# pinoccio-motion.net
KiCad netlist of a schematic drawn in EAGLE
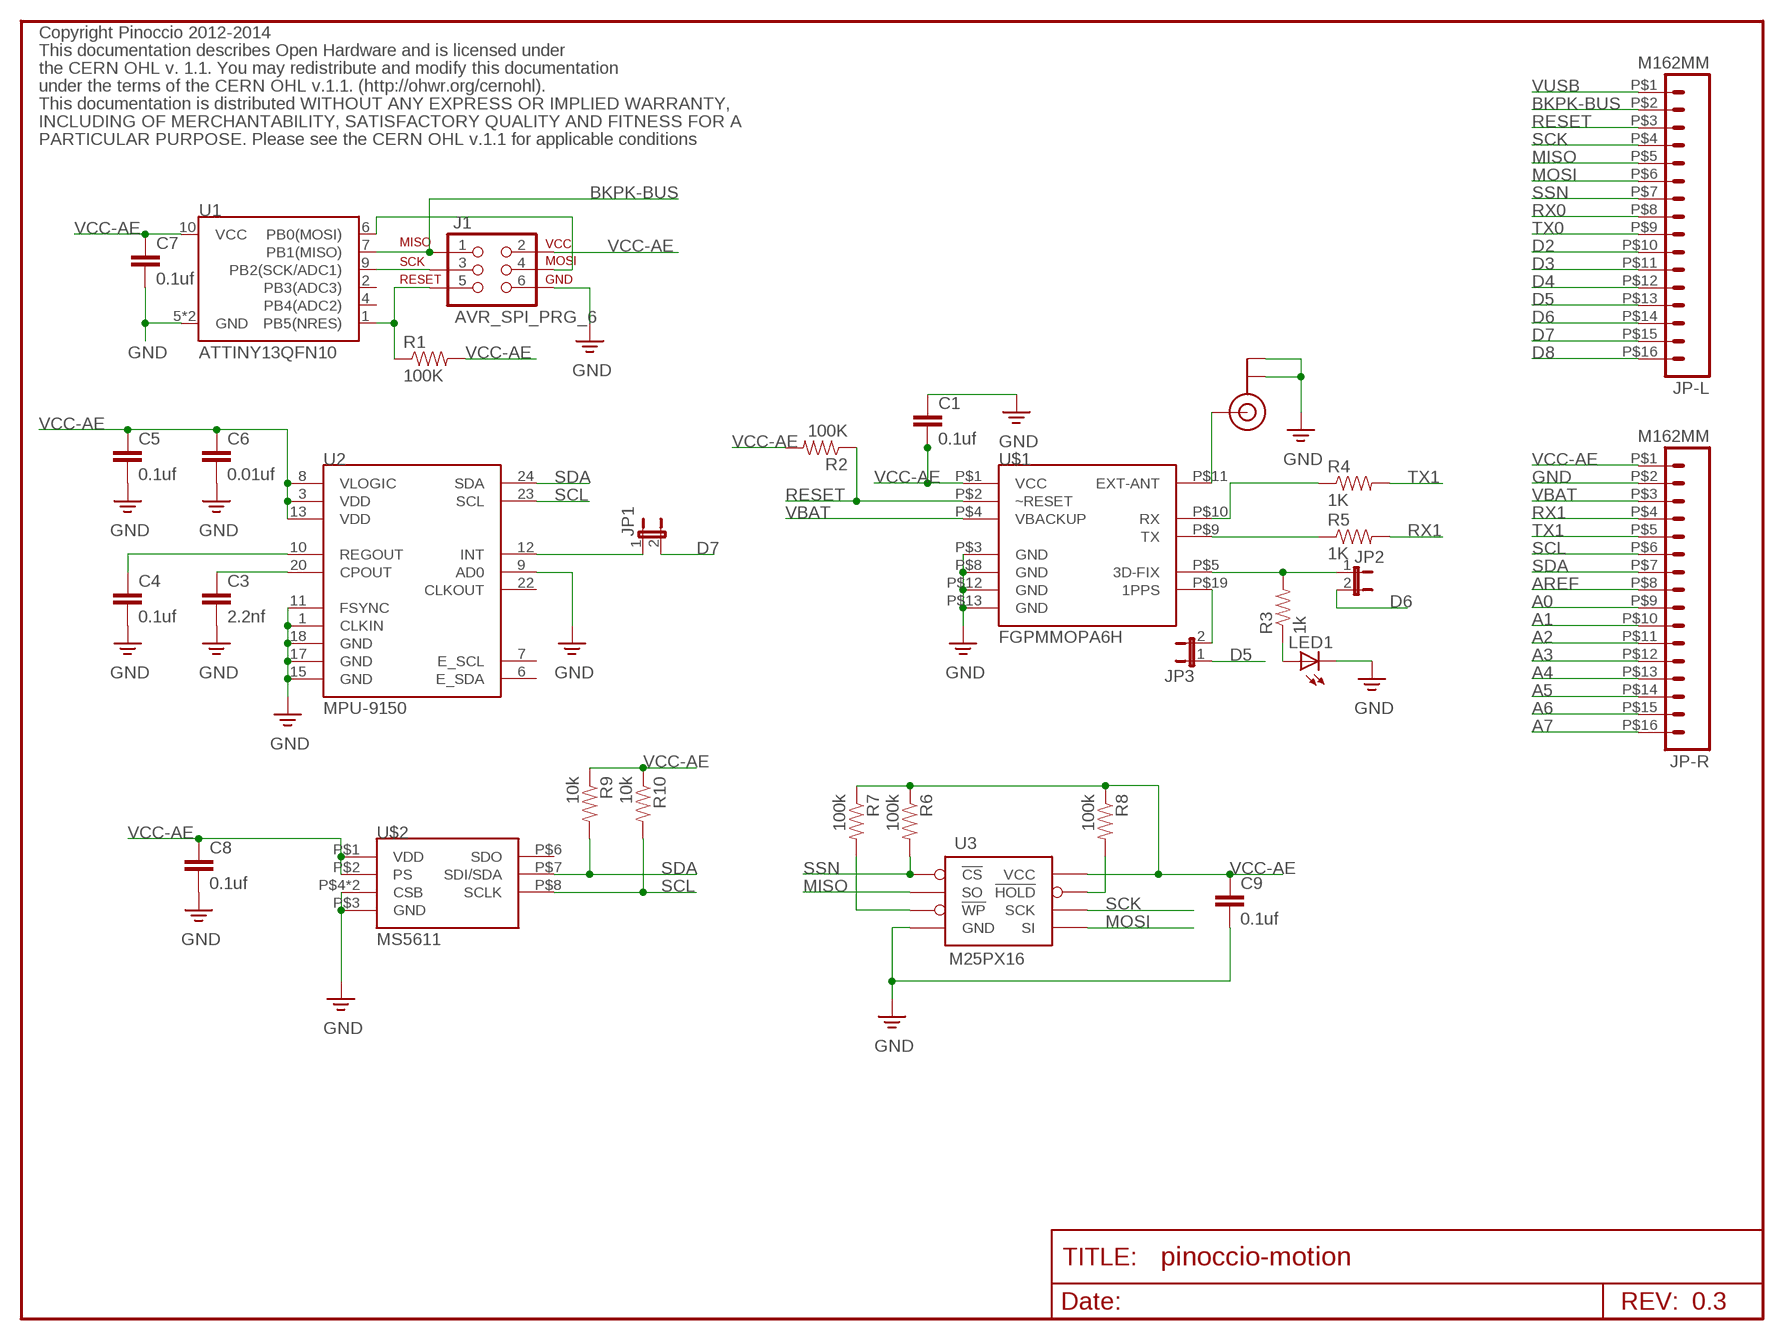
[diagram p0: schematic, sheet 1]

(export (version "E")
  (design (tool "Eeschema 10.0.6"))
  (components
    (comp (ref "C1")
      (value "0.1uf")
      (footprint "eagle-import:0402-CAP")
      (libsource (lib "eagle-import") (part "CAP0402-CAP"))
    )
    (comp (ref "C3")
      (value "2.2nf")
      (footprint "eagle-import:0603-CAP")
      (libsource (lib "eagle-import") (part "CAP0603-CAP"))
    )
    (comp (ref "C4")
      (value "0.1uf")
      (footprint "eagle-import:0402-CAP")
      (libsource (lib "eagle-import") (part "CAP0402-CAP"))
    )
    (comp (ref "C5")
      (value "0.1uf")
      (footprint "eagle-import:0402-CAP")
      (libsource (lib "eagle-import") (part "CAP0402-CAP"))
    )
    (comp (ref "C6")
      (value "0.01uf")
      (footprint "eagle-import:0402-CAP")
      (libsource (lib "eagle-import") (part "CAP0402-CAP"))
    )
    (comp (ref "C7")
      (value "0.1uf")
      (footprint "eagle-import:0402-CAP")
      (libsource (lib "eagle-import") (part "CAP0402-CAP"))
    )
    (comp (ref "C8")
      (value "0.1uf")
      (footprint "eagle-import:0402-CAP")
      (libsource (lib "eagle-import") (part "CAP0402-CAP"))
    )
    (comp (ref "C9")
      (value "0.1uf")
      (footprint "eagle-import:0402-CAP")
      (libsource (lib "eagle-import") (part "CAP0402-CAP"))
    )
    (comp (ref "J1")
      (value "AVR_SPI_PRG_6")
      (footprint "eagle-import:2X3-PAD")
      (libsource (lib "eagle-import") (part "AVR_SPI_PRG_6"))
    )
    (comp (ref "JP-L")
      (value "M162MM")
      (footprint "eagle-import:1X16_2MM")
      (libsource (lib "eagle-import") (part "M162MM"))
    )
    (comp (ref "JP-R")
      (value "M162MM")
      (footprint "eagle-import:1X16_2MM")
      (libsource (lib "eagle-import") (part "M162MM"))
    )
    (comp (ref "JP1")
      (value "JUMPER-2SMD-NC")
      (footprint "eagle-import:SJ_2S")
      (libsource (lib "eagle-import") (part "JUMPER-2SMD-NC"))
    )
    (comp (ref "JP2")
      (value "JUMPER-2SMD-NC")
      (footprint "eagle-import:SJ_2S")
      (libsource (lib "eagle-import") (part "JUMPER-2SMD-NC"))
    )
    (comp (ref "JP3")
      (value "JUMPER-2SMD-NC")
      (footprint "eagle-import:SJ_2S")
      (libsource (lib "eagle-import") (part "JUMPER-2SMD-NC"))
    )
    (comp (ref "LED1")
      (value "LED0603")
      (footprint "eagle-import:LED-0603")
      (libsource (lib "eagle-import") (part "LED0603"))
    )
    (comp (ref "R1")
      (value "100K")
      (footprint "eagle-import:0402-RES")
      (libsource (lib "eagle-import") (part "RESISTOR0402-RES"))
    )
    (comp (ref "R2")
      (value "100K")
      (footprint "eagle-import:0402-RES")
      (libsource (lib "eagle-import") (part "RESISTOR0402-RES"))
    )
    (comp (ref "R3")
      (value "1k")
      (footprint "eagle-import:0402-RES")
      (libsource (lib "eagle-import") (part "RESISTOR0402-RES"))
    )
    (comp (ref "R4")
      (value "1K")
      (footprint "eagle-import:0402-RES")
      (libsource (lib "eagle-import") (part "RESISTOR0402-RES"))
    )
    (comp (ref "R5")
      (value "1K")
      (footprint "eagle-import:0402-RES")
      (libsource (lib "eagle-import") (part "RESISTOR0402-RES"))
    )
    (comp (ref "R6")
      (value "100k")
      (footprint "eagle-import:0402-RES")
      (libsource (lib "eagle-import") (part "RESISTOR0402-RES"))
    )
    (comp (ref "R7")
      (value "100k")
      (footprint "eagle-import:0402-RES")
      (libsource (lib "eagle-import") (part "RESISTOR0402-RES"))
    )
    (comp (ref "R8")
      (value "100k")
      (footprint "eagle-import:0402-RES")
      (libsource (lib "eagle-import") (part "RESISTOR0402-RES"))
    )
    (comp (ref "R9")
      (value "10k")
      (footprint "eagle-import:0402-RES")
      (libsource (lib "eagle-import") (part "RESISTOR0402-RES"))
    )
    (comp (ref "R10")
      (value "10k")
      (footprint "eagle-import:0402-RES")
      (libsource (lib "eagle-import") (part "RESISTOR0402-RES"))
    )
    (comp (ref "U$1")
      (value "FGPMMOPA6H")
      (footprint "eagle-import:FGPMMOPA6H")
      (libsource (lib "eagle-import") (part "FGPMMOPA6H"))
    )
    (comp (ref "U$2")
      (value "MS5611")
      (footprint "eagle-import:MS5611")
      (libsource (lib "eagle-import") (part "MS5611"))
    )
    (comp (ref "U$4")
      (value "U.FL")
      (footprint "eagle-import:U.FL")
      (libsource (lib "eagle-import") (part "U.FL"))
    )
    (comp (ref "U1")
      (value "ATTINY13QFN10")
      (footprint "eagle-import:QFN-10")
      (libsource (lib "eagle-import") (part "ATTINY13QFN10"))
    )
    (comp (ref "U2")
      (value "MPU-9150")
      (footprint "eagle-import:QFN-24-NP")
      (libsource (lib "eagle-import") (part "MPU-9150QFN-24-NP"))
    )
    (comp (ref "U3")
      (value "M25PX16")
      (footprint "eagle-import:SO8N")
      (libsource (lib "eagle-import") (part "M25PX16SO8N"))
    )
  )
  (nets
    (net (code "1") (name "/A0") (class "Default")
      (node (ref "JP-R") (pin "P$9") (pinfunction "9_P$9") (pintype "passive"))
    )
    (net (code "2") (name "/A1") (class "Default")
      (node (ref "JP-R") (pin "P$10") (pinfunction "10_P$10") (pintype "passive"))
    )
    (net (code "3") (name "/A2") (class "Default")
      (node (ref "JP-R") (pin "P$11") (pinfunction "11_P$11") (pintype "passive"))
    )
    (net (code "4") (name "/A3") (class "Default")
      (node (ref "JP-R") (pin "P$12") (pinfunction "12_P$12") (pintype "passive"))
    )
    (net (code "5") (name "/A4") (class "Default")
      (node (ref "JP-R") (pin "P$13") (pinfunction "13_P$13") (pintype "passive"))
    )
    (net (code "6") (name "/A5") (class "Default")
      (node (ref "JP-R") (pin "P$14") (pinfunction "14_P$14") (pintype "passive"))
    )
    (net (code "7") (name "/A6") (class "Default")
      (node (ref "JP-R") (pin "P$15") (pinfunction "15_P$15") (pintype "passive"))
    )
    (net (code "8") (name "/A7") (class "Default")
      (node (ref "JP-R") (pin "P$16") (pinfunction "16_P$16") (pintype "passive"))
    )
    (net (code "9") (name "/AREF") (class "Default")
      (node (ref "JP-R") (pin "P$8") (pinfunction "8_P$8") (pintype "passive"))
    )
    (net (code "10") (name "/BKPK-BUS") (class "Default")
      (node (ref "J1") (pin "1") (pinfunction "1_1") (pintype "passive"))
      (node (ref "JP-L") (pin "P$2") (pinfunction "2_P$2") (pintype "passive"))
      (node (ref "U1") (pin "7") (pinfunction "PB1(MISO)_7") (pintype "bidirectional"))
    )
    (net (code "11") (name "/D2") (class "Default")
      (node (ref "JP-L") (pin "P$10") (pinfunction "10_P$10") (pintype "passive"))
    )
    (net (code "12") (name "/D3") (class "Default")
      (node (ref "JP-L") (pin "P$11") (pinfunction "11_P$11") (pintype "passive"))
    )
    (net (code "13") (name "/D4") (class "Default")
      (node (ref "JP-L") (pin "P$12") (pinfunction "12_P$12") (pintype "passive"))
    )
    (net (code "14") (name "/D5") (class "Default")
      (node (ref "JP-L") (pin "P$13") (pinfunction "13_P$13") (pintype "passive"))
      (node (ref "JP3") (pin "1") (pinfunction "1_1") (pintype "passive"))
    )
    (net (code "15") (name "/D6") (class "Default")
      (node (ref "JP-L") (pin "P$14") (pinfunction "14_P$14") (pintype "passive"))
      (node (ref "JP2") (pin "2") (pinfunction "2_2") (pintype "passive"))
    )
    (net (code "16") (name "/D7") (class "Default")
      (node (ref "JP-L") (pin "P$15") (pinfunction "15_P$15") (pintype "passive"))
      (node (ref "JP1") (pin "2") (pinfunction "2_2") (pintype "passive"))
    )
    (net (code "17") (name "/D8") (class "Default")
      (node (ref "JP-L") (pin "P$16") (pinfunction "16_P$16") (pintype "passive"))
    )
    (net (code "18") (name "/MISO") (class "Default")
      (node (ref "JP-L") (pin "P$5") (pinfunction "5_P$5") (pintype "passive"))
      (node (ref "U3") (pin "2") (pinfunction "SO_2") (pintype "bidirectional"))
    )
    (net (code "19") (name "/MOSI") (class "Default")
      (node (ref "JP-L") (pin "P$6") (pinfunction "6_P$6") (pintype "passive"))
      (node (ref "U3") (pin "5") (pinfunction "SI_5") (pintype "bidirectional"))
    )
    (net (code "20") (name "/RESET") (class "Default")
      (node (ref "JP-L") (pin "P$3") (pinfunction "3_P$3") (pintype "passive"))
      (node (ref "R2") (pin "1") (pinfunction "1_1") (pintype "passive"))
      (node (ref "U$1") (pin "P$2") (pinfunction "~{RESET}_P$2") (pintype "bidirectional"))
    )
    (net (code "21") (name "/RX0") (class "Default")
      (node (ref "JP-L") (pin "P$8") (pinfunction "8_P$8") (pintype "passive"))
    )
    (net (code "22") (name "/RX1") (class "Default")
      (node (ref "JP-R") (pin "P$4") (pinfunction "4_P$4") (pintype "passive"))
      (node (ref "R5") (pin "2") (pinfunction "2_2") (pintype "passive"))
    )
    (net (code "23") (name "/SCK") (class "Default")
      (node (ref "JP-L") (pin "P$4") (pinfunction "4_P$4") (pintype "passive"))
      (node (ref "U3") (pin "6") (pinfunction "SCK_6") (pintype "bidirectional"))
    )
    (net (code "24") (name "/SCL") (class "Default")
      (node (ref "JP-R") (pin "P$6") (pinfunction "6_P$6") (pintype "passive"))
      (node (ref "R10") (pin "2") (pinfunction "2_2") (pintype "passive"))
      (node (ref "U$2") (pin "P$8") (pinfunction "SCLK_P$8") (pintype "bidirectional"))
      (node (ref "U2") (pin "23") (pinfunction "SCL_23") (pintype "bidirectional"))
    )
    (net (code "25") (name "/SDA") (class "Default")
      (node (ref "JP-R") (pin "P$7") (pinfunction "7_P$7") (pintype "passive"))
      (node (ref "R9") (pin "2") (pinfunction "2_2") (pintype "passive"))
      (node (ref "U$2") (pin "P$7") (pinfunction "SDI/SDA_P$7") (pintype "bidirectional"))
      (node (ref "U2") (pin "24") (pinfunction "SDA_24") (pintype "bidirectional"))
    )
    (net (code "26") (name "/SSN") (class "Default")
      (node (ref "JP-L") (pin "P$7") (pinfunction "7_P$7") (pintype "passive"))
      (node (ref "R6") (pin "2") (pinfunction "2_2") (pintype "passive"))
      (node (ref "U3") (pin "1") (pinfunction "~{CS}_1") (pintype "bidirectional"))
    )
    (net (code "27") (name "/TX0") (class "Default")
      (node (ref "JP-L") (pin "P$9") (pinfunction "9_P$9") (pintype "passive"))
    )
    (net (code "28") (name "/TX1") (class "Default")
      (node (ref "JP-R") (pin "P$5") (pinfunction "5_P$5") (pintype "passive"))
      (node (ref "R4") (pin "2") (pinfunction "2_2") (pintype "passive"))
    )
    (net (code "29") (name "/VBAT") (class "Default")
      (node (ref "JP-R") (pin "P$3") (pinfunction "3_P$3") (pintype "passive"))
      (node (ref "U$1") (pin "P$4") (pinfunction "VBACKUP_P$4") (pintype "bidirectional"))
    )
    (net (code "30") (name "/VCC-AE") (class "Default")
      (node (ref "C1") (pin "2") (pinfunction "2_2") (pintype "passive"))
      (node (ref "C5") (pin "1") (pinfunction "1_1") (pintype "passive"))
      (node (ref "C6") (pin "1") (pinfunction "1_1") (pintype "passive"))
      (node (ref "C7") (pin "1") (pinfunction "1_1") (pintype "passive"))
      (node (ref "C8") (pin "1") (pinfunction "1_1") (pintype "passive"))
      (node (ref "C9") (pin "1") (pinfunction "1_1") (pintype "passive"))
      (node (ref "J1") (pin "2") (pinfunction "2_2") (pintype "passive"))
      (node (ref "JP-R") (pin "P$1") (pinfunction "1_P$1") (pintype "passive"))
      (node (ref "R1") (pin "2") (pinfunction "2_2") (pintype "passive"))
      (node (ref "R10") (pin "1") (pinfunction "1_1") (pintype "passive"))
      (node (ref "R2") (pin "2") (pinfunction "2_2") (pintype "passive"))
      (node (ref "R6") (pin "1") (pinfunction "1_1") (pintype "passive"))
      (node (ref "R7") (pin "1") (pinfunction "1_1") (pintype "passive"))
      (node (ref "R8") (pin "1") (pinfunction "1_1") (pintype "passive"))
      (node (ref "R9") (pin "1") (pinfunction "1_1") (pintype "passive"))
      (node (ref "U$1") (pin "P$1") (pinfunction "VCC_P$1") (pintype "bidirectional"))
      (node (ref "U$2") (pin "P$1") (pinfunction "VDD_P$1") (pintype "bidirectional"))
      (node (ref "U$2") (pin "P$2") (pinfunction "PS_P$2") (pintype "bidirectional"))
      (node (ref "U1") (pin "10") (pinfunction "VCC_10") (pintype "bidirectional"))
      (node (ref "U2") (pin "13") (pinfunction "VDD_13") (pintype "bidirectional"))
      (node (ref "U2") (pin "3") (pinfunction "VDD_3") (pintype "bidirectional"))
      (node (ref "U2") (pin "8") (pinfunction "VLOGIC_8") (pintype "bidirectional"))
      (node (ref "U3") (pin "8") (pinfunction "VCC_8") (pintype "bidirectional"))
    )
    (net (code "31") (name "/VUSB") (class "Default")
      (node (ref "JP-L") (pin "P$1") (pinfunction "1_P$1") (pintype "passive"))
    )
    (net (code "32") (name "GND") (class "Default")
      (node (ref "C1") (pin "1") (pinfunction "1_1") (pintype "passive"))
      (node (ref "C3") (pin "2") (pinfunction "2_2") (pintype "passive"))
      (node (ref "C4") (pin "2") (pinfunction "2_2") (pintype "passive"))
      (node (ref "C5") (pin "2") (pinfunction "2_2") (pintype "passive"))
      (node (ref "C6") (pin "2") (pinfunction "2_2") (pintype "passive"))
      (node (ref "C7") (pin "2") (pinfunction "2_2") (pintype "passive"))
      (node (ref "C8") (pin "2") (pinfunction "2_2") (pintype "passive"))
      (node (ref "C9") (pin "2") (pinfunction "2_2") (pintype "passive"))
      (node (ref "J1") (pin "6") (pinfunction "6_6") (pintype "passive"))
      (node (ref "JP-R") (pin "P$2") (pinfunction "2_P$2") (pintype "passive"))
      (node (ref "LED1") (pin "C") (pinfunction "C_C") (pintype "passive"))
      (node (ref "U$1") (pin "P$12") (pinfunction "GND_P$12") (pintype "bidirectional"))
      (node (ref "U$1") (pin "P$13") (pinfunction "GND_P$13") (pintype "bidirectional"))
      (node (ref "U$1") (pin "P$3") (pinfunction "GND_P$3") (pintype "bidirectional"))
      (node (ref "U$1") (pin "P$8") (pinfunction "GND_P$8") (pintype "bidirectional"))
      (node (ref "U$2") (pin "P$3") (pinfunction "GND_P$3") (pintype "bidirectional"))
      (node (ref "U$2") (pin "P$4") (pinfunction "CSB_P$4") (pintype "bidirectional"))
      (node (ref "U$2") (pin "P$5") (pinfunction "CSB_P$5") (pintype "bidirectional"))
      (node (ref "U$4") (pin "P$1") (pinfunction "GND_P$1") (pintype "bidirectional"))
      (node (ref "U$4") (pin "P$2") (pinfunction "GND_P$2") (pintype "bidirectional"))
      (node (ref "U1") (pin "5") (pinfunction "GND_5") (pintype "bidirectional"))
      (node (ref "U1") (pin "EP") (pinfunction "GND_EP") (pintype "bidirectional"))
      (node (ref "U2") (pin "1") (pinfunction "CLKIN_1") (pintype "bidirectional"))
      (node (ref "U2") (pin "11") (pinfunction "FSYNC_11") (pintype "bidirectional"))
      (node (ref "U2") (pin "15") (pinfunction "GND_15") (pintype "bidirectional"))
      (node (ref "U2") (pin "17") (pinfunction "GND_17") (pintype "bidirectional"))
      (node (ref "U2") (pin "18") (pinfunction "GND_18") (pintype "bidirectional"))
      (node (ref "U2") (pin "9") (pinfunction "AD0_9") (pintype "bidirectional"))
      (node (ref "U3") (pin "4") (pinfunction "GND_4") (pintype "bidirectional"))
    )
    (net (code "33") (name "Net-(LED1-PadA)") (class "Default")
      (node (ref "LED1") (pin "A") (pinfunction "A_A") (pintype "passive"))
      (node (ref "R3") (pin "1") (pinfunction "1_1") (pintype "passive"))
    )
    (net (code "34") (name "Net-(U$1-1PPS)") (class "Default")
      (node (ref "JP3") (pin "2") (pinfunction "2_2") (pintype "passive"))
      (node (ref "U$1") (pin "P$19") (pinfunction "1PPS_P$19") (pintype "bidirectional"))
    )
    (net (code "35") (name "Net-(U$1-3D-FIX)") (class "Default")
      (node (ref "JP2") (pin "1") (pinfunction "1_1") (pintype "passive"))
      (node (ref "R3") (pin "2") (pinfunction "2_2") (pintype "passive"))
      (node (ref "U$1") (pin "P$5") (pinfunction "3D-FIX_P$5") (pintype "bidirectional"))
    )
    (net (code "36") (name "Net-(U$1-EXT-ANT)") (class "Default")
      (node (ref "U$1") (pin "P$11") (pinfunction "EXT-ANT_P$11") (pintype "bidirectional"))
      (node (ref "U$4") (pin "P$3") (pinfunction "SIGNAL_P$3") (pintype "bidirectional"))
    )
    (net (code "37") (name "Net-(U$1-RX)") (class "Default")
      (node (ref "R4") (pin "1") (pinfunction "1_1") (pintype "passive"))
      (node (ref "U$1") (pin "P$10") (pinfunction "RX_P$10") (pintype "bidirectional"))
    )
    (net (code "38") (name "Net-(U$1-TX)") (class "Default")
      (node (ref "R5") (pin "1") (pinfunction "1_1") (pintype "passive"))
      (node (ref "U$1") (pin "P$9") (pinfunction "TX_P$9") (pintype "bidirectional"))
    )
    (net (code "39") (name "Net-(U1-PB0(MOSI))") (class "Default")
      (node (ref "J1") (pin "4") (pinfunction "4_4") (pintype "passive"))
      (node (ref "U1") (pin "6") (pinfunction "PB0(MOSI)_6") (pintype "bidirectional"))
    )
    (net (code "40") (name "Net-(U1-PB2(SCK{slash}ADC1))") (class "Default")
      (node (ref "J1") (pin "3") (pinfunction "3_3") (pintype "passive"))
      (node (ref "U1") (pin "9") (pinfunction "PB2(SCK/ADC1)_9") (pintype "bidirectional"))
    )
    (net (code "41") (name "Net-(U1-PB5(NRES))") (class "Default")
      (node (ref "J1") (pin "5") (pinfunction "5_5") (pintype "passive"))
      (node (ref "R1") (pin "1") (pinfunction "1_1") (pintype "passive"))
      (node (ref "U1") (pin "1") (pinfunction "PB5(NRES)_1") (pintype "bidirectional"))
    )
    (net (code "42") (name "Net-(U2-CPOUT)") (class "Default")
      (node (ref "C3") (pin "1") (pinfunction "1_1") (pintype "passive"))
      (node (ref "U2") (pin "20") (pinfunction "CPOUT_20") (pintype "bidirectional"))
    )
    (net (code "43") (name "Net-(U2-INT)") (class "Default")
      (node (ref "JP1") (pin "1") (pinfunction "1_1") (pintype "passive"))
      (node (ref "U2") (pin "12") (pinfunction "INT_12") (pintype "bidirectional"))
    )
    (net (code "44") (name "Net-(U2-REGOUT)") (class "Default")
      (node (ref "C4") (pin "1") (pinfunction "1_1") (pintype "passive"))
      (node (ref "U2") (pin "10") (pinfunction "REGOUT_10") (pintype "bidirectional"))
    )
    (net (code "45") (name "Net-(U3-~{HOLD})") (class "Default")
      (node (ref "R8") (pin "2") (pinfunction "2_2") (pintype "passive"))
      (node (ref "U3") (pin "7") (pinfunction "~{HOLD}_7") (pintype "bidirectional"))
    )
    (net (code "46") (name "Net-(U3-~{WP})") (class "Default")
      (node (ref "R7") (pin "2") (pinfunction "2_2") (pintype "passive"))
      (node (ref "U3") (pin "3") (pinfunction "~{WP}_3") (pintype "bidirectional"))
    )
    (net (code "47") (name "unconnected-(U$2-SDO-PadP$6)") (class "Default")
      (node (ref "U$2") (pin "P$6") (pinfunction "SDO_P$6") (pintype "bidirectional"))
    )
    (net (code "48") (name "unconnected-(U1-PB3(ADC3)-Pad2)") (class "Default")
      (node (ref "U1") (pin "2") (pinfunction "PB3(ADC3)_2") (pintype "bidirectional"))
    )
    (net (code "49") (name "unconnected-(U1-PB4(ADC2)-Pad4)") (class "Default")
      (node (ref "U1") (pin "4") (pinfunction "PB4(ADC2)_4") (pintype "bidirectional"))
    )
    (net (code "50") (name "unconnected-(U2-CLKOUT-Pad22)") (class "Default")
      (node (ref "U2") (pin "22") (pinfunction "CLKOUT_22") (pintype "bidirectional"))
    )
    (net (code "51") (name "unconnected-(U2-E_SCL-Pad7)") (class "Default")
      (node (ref "U2") (pin "7") (pinfunction "E_SCL_7") (pintype "bidirectional"))
    )
    (net (code "52") (name "unconnected-(U2-E_SDA-Pad6)") (class "Default")
      (node (ref "U2") (pin "6") (pinfunction "E_SDA_6") (pintype "bidirectional"))
    )
  )
)
